# STM32f103.net
KiCad netlist of a schematic drawn in EAGLE
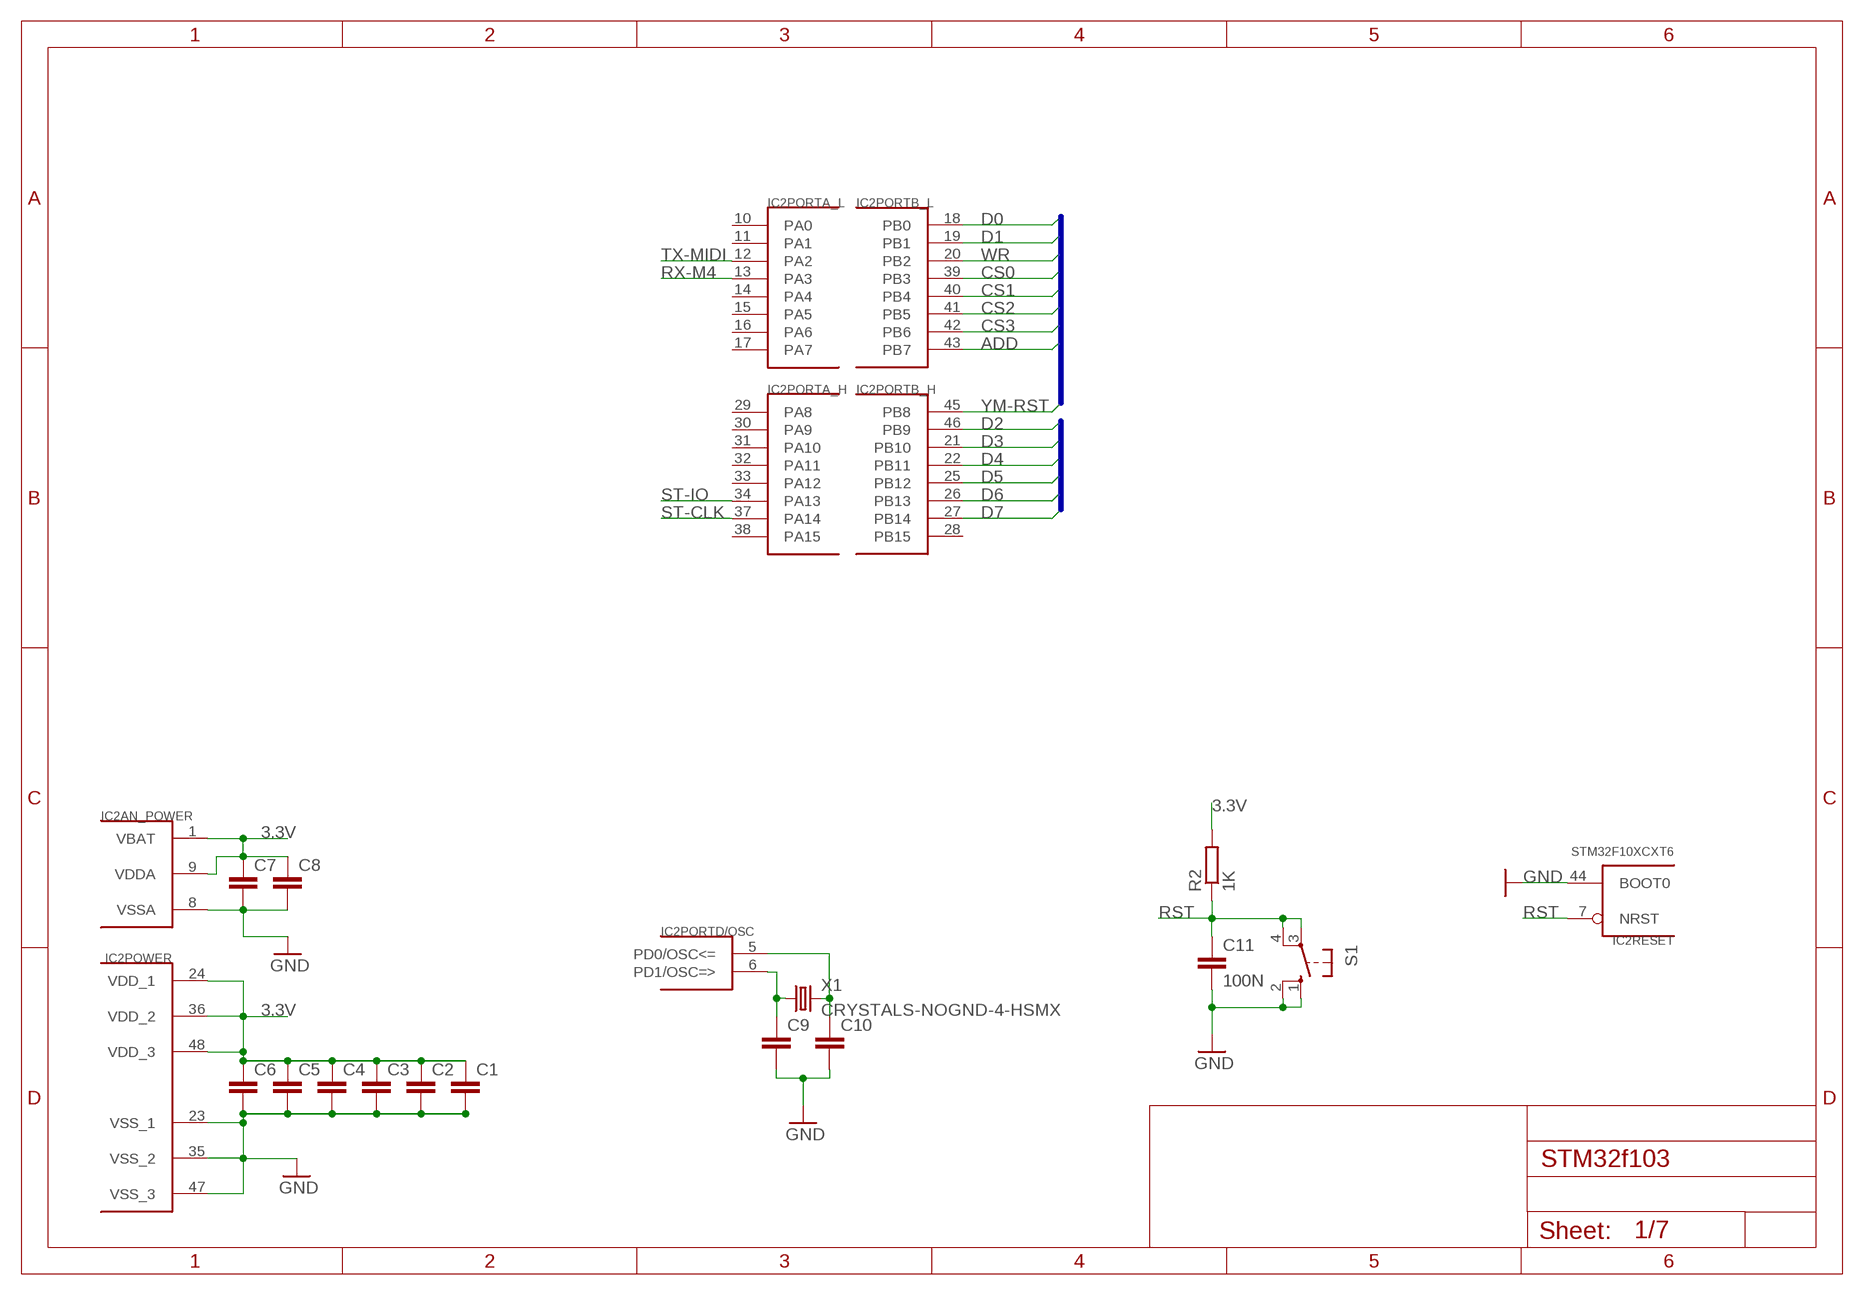
[diagram p0: schematic, sheet 1]
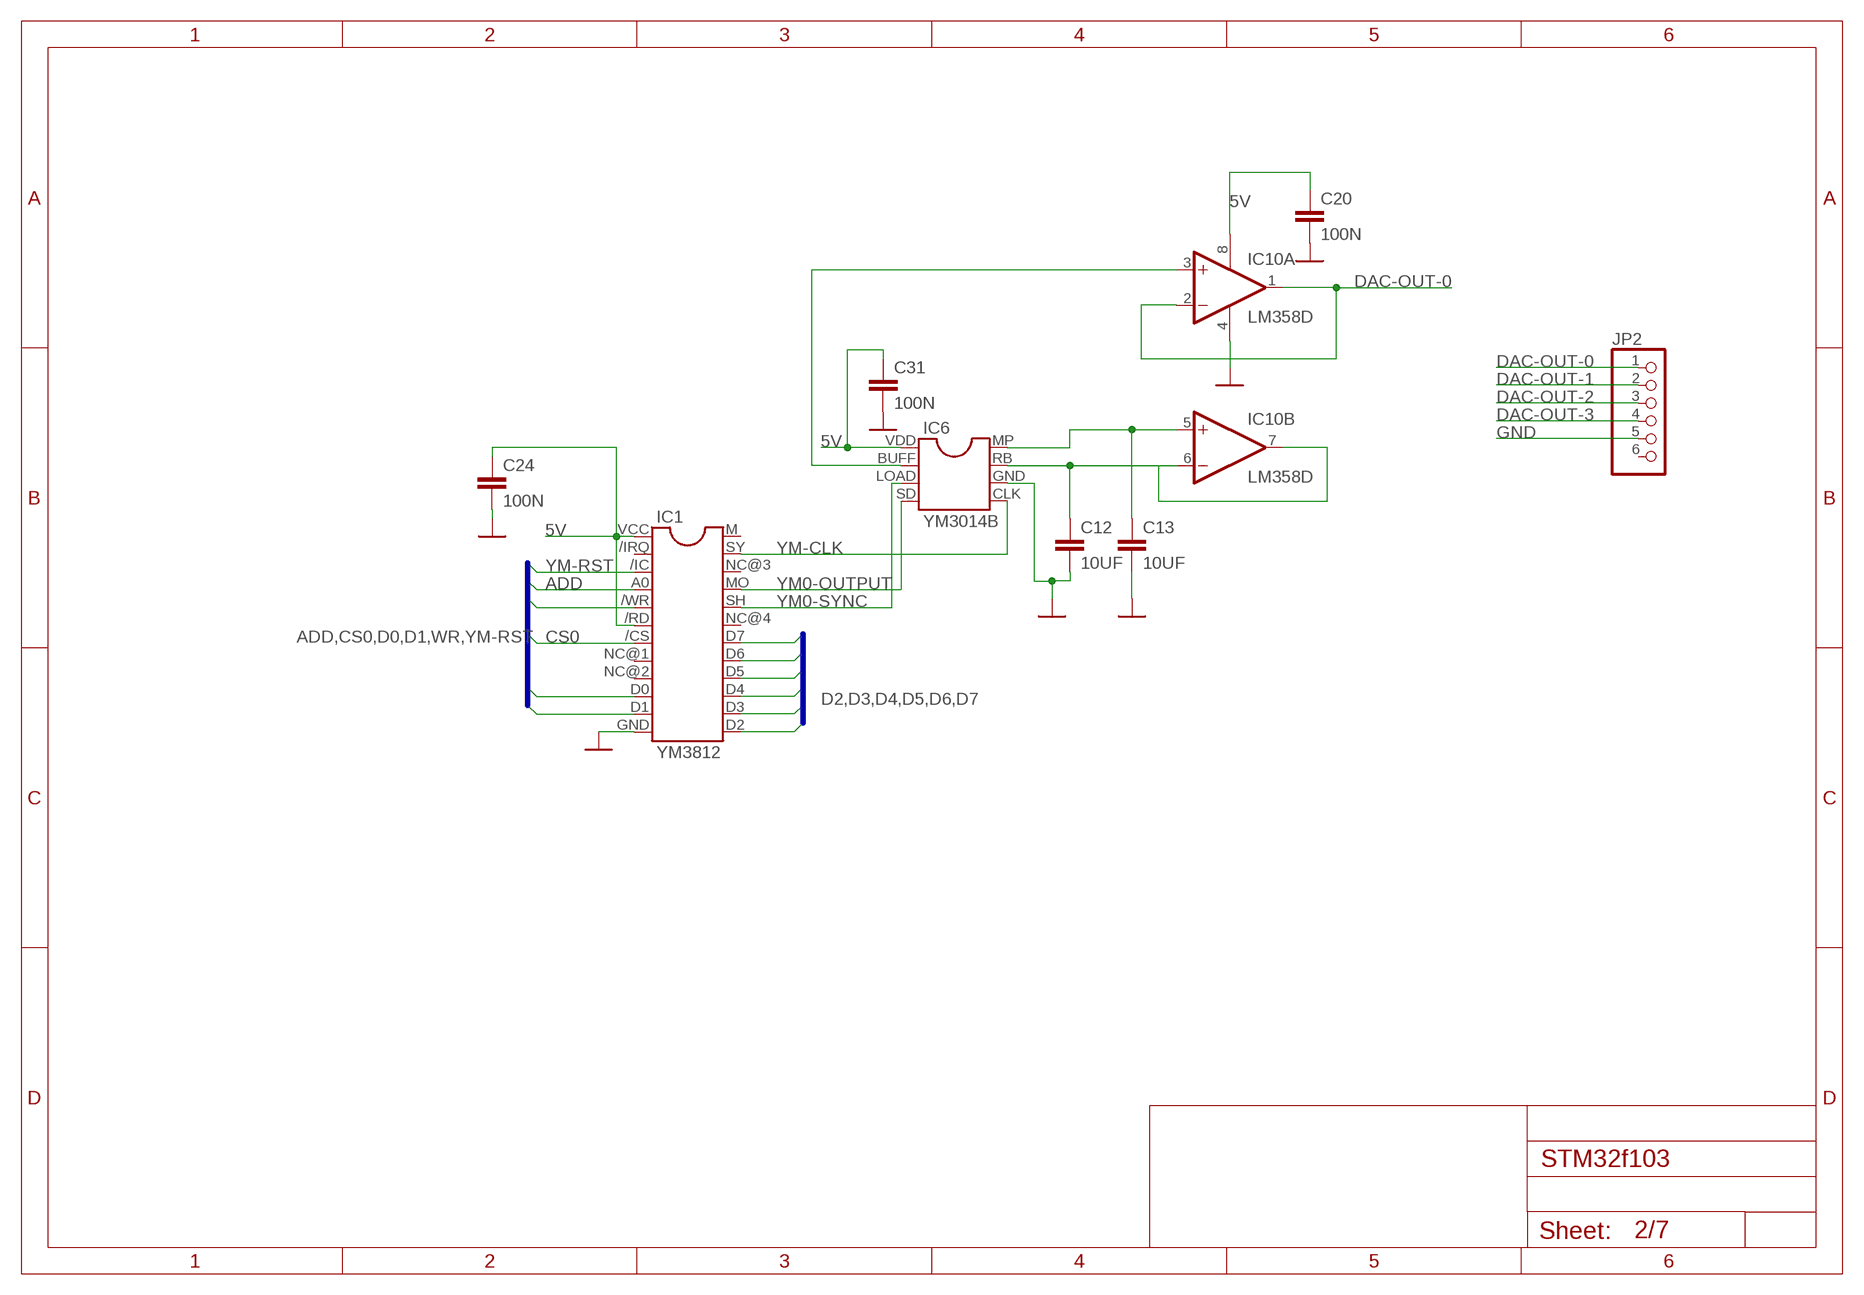
[diagram p1: schematic, sheet 2]
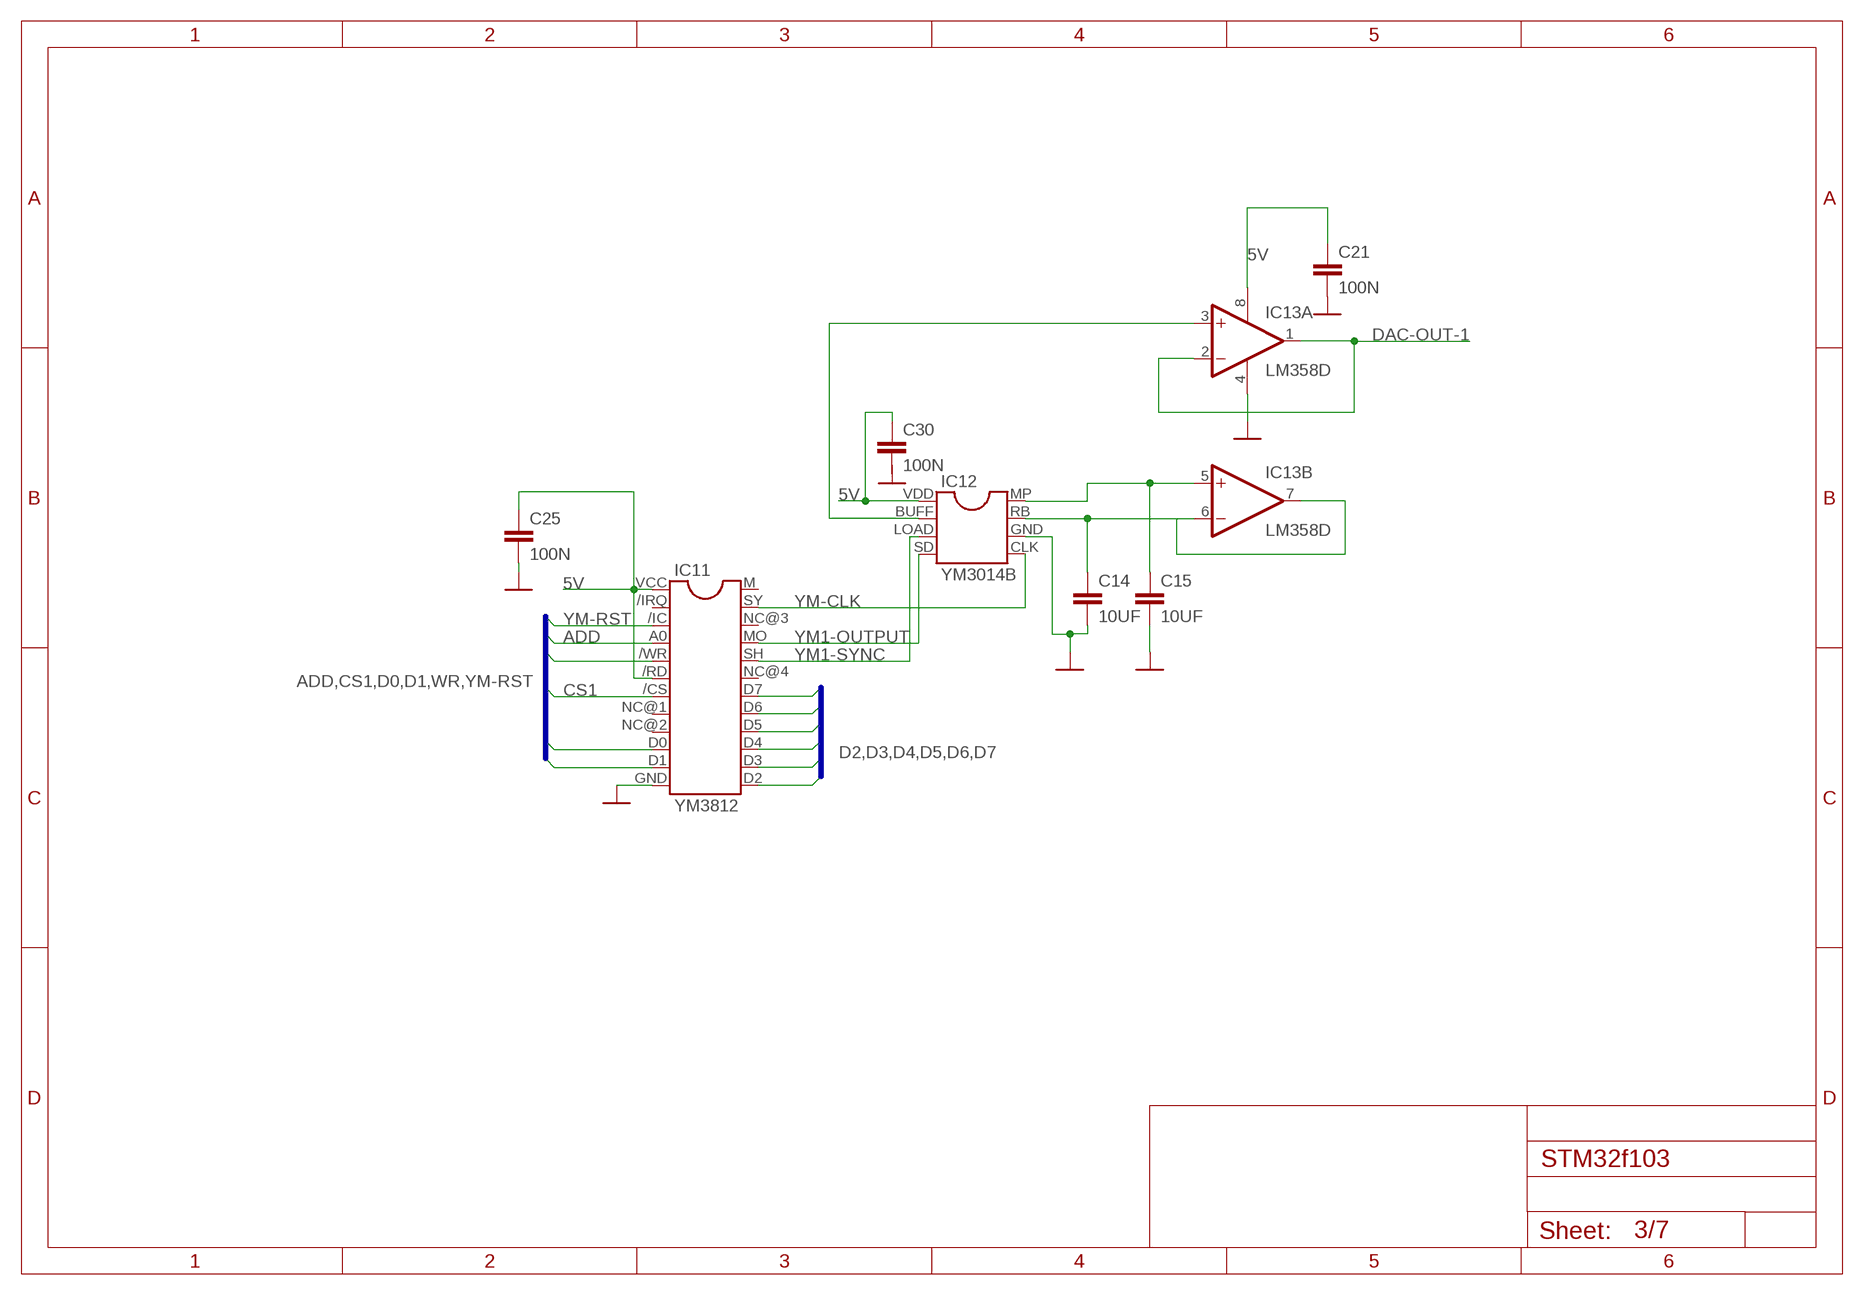
[diagram p2: schematic, sheet 3]
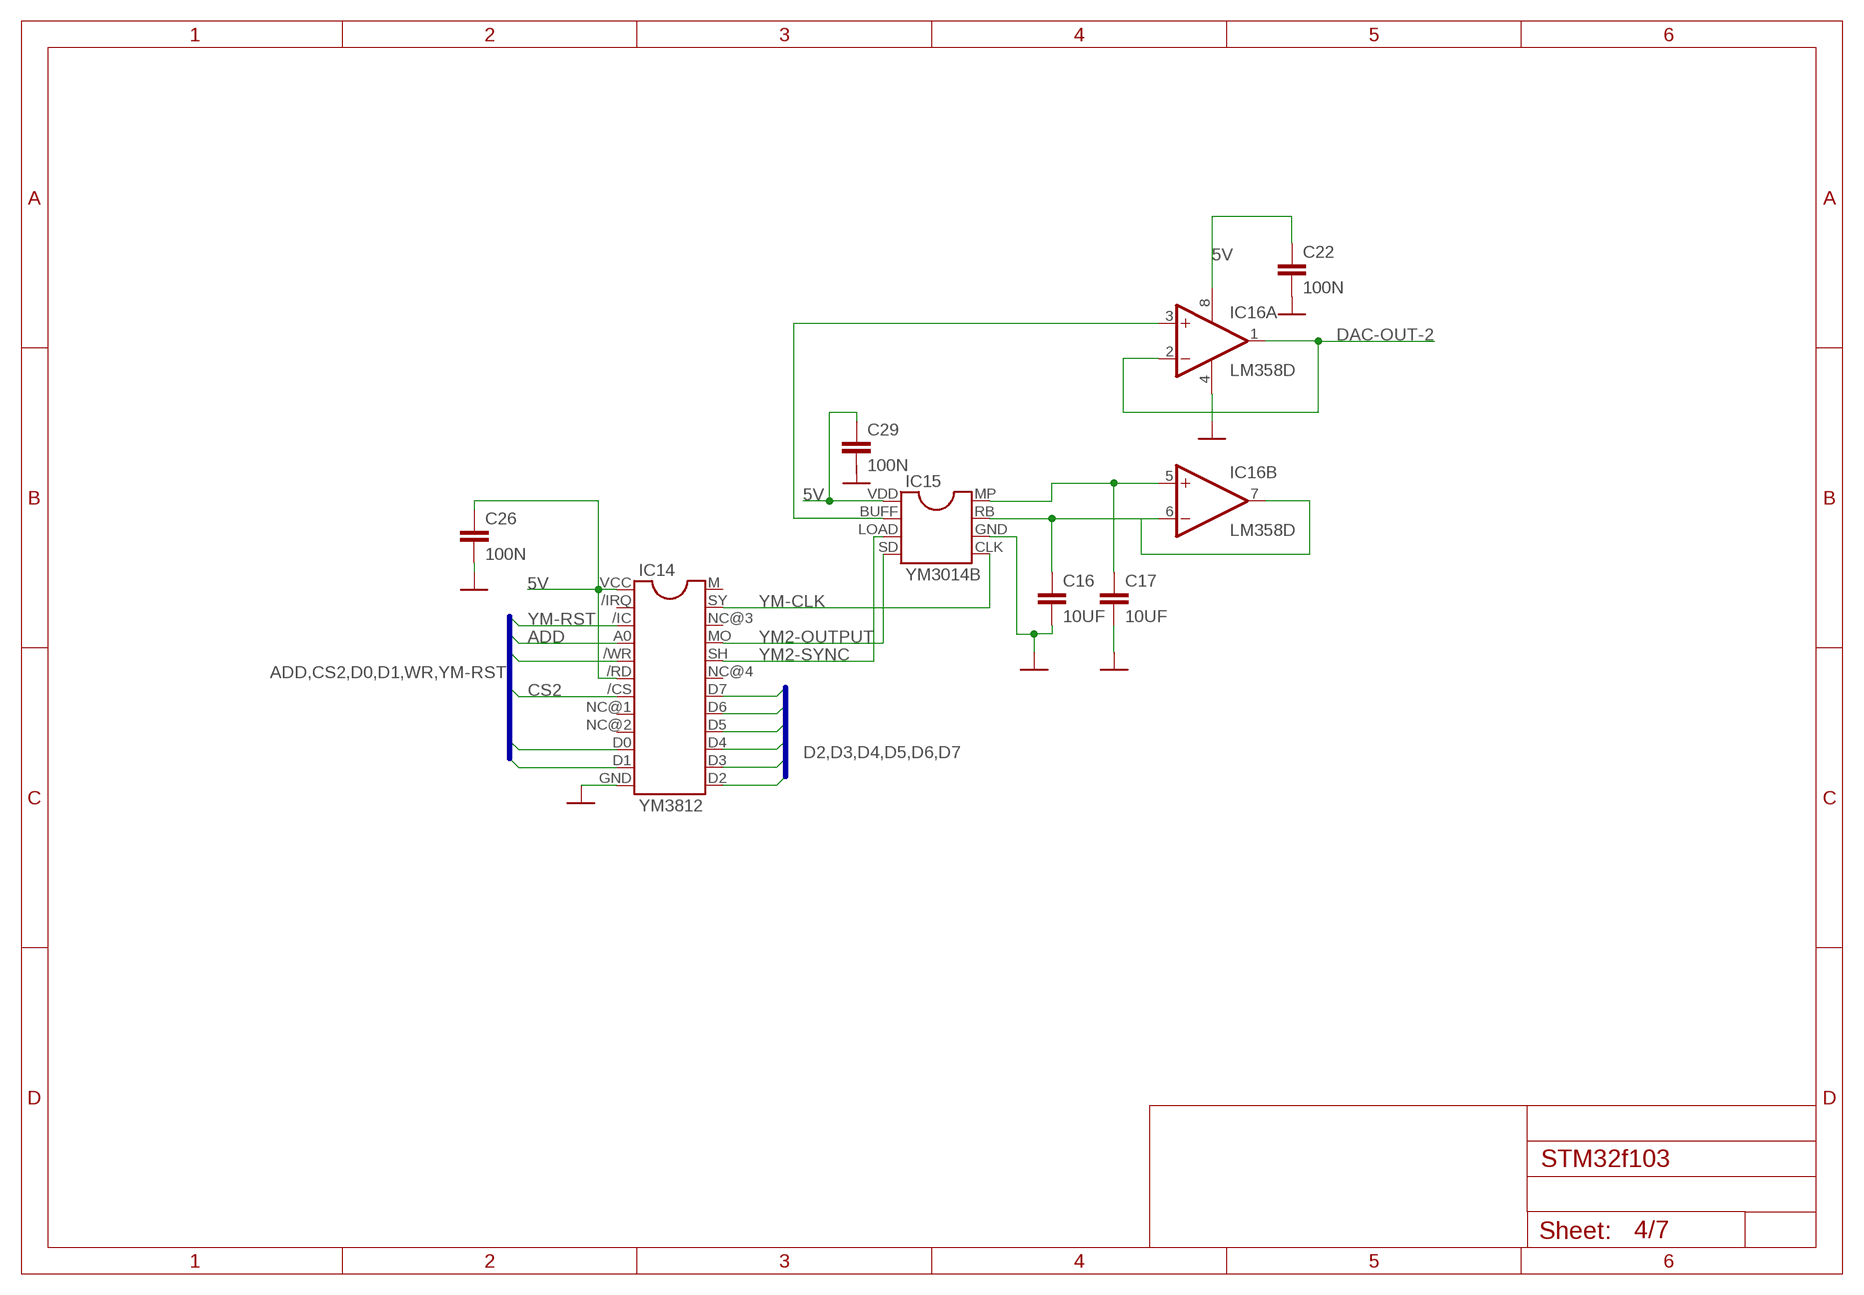
[diagram p3: schematic, sheet 4]
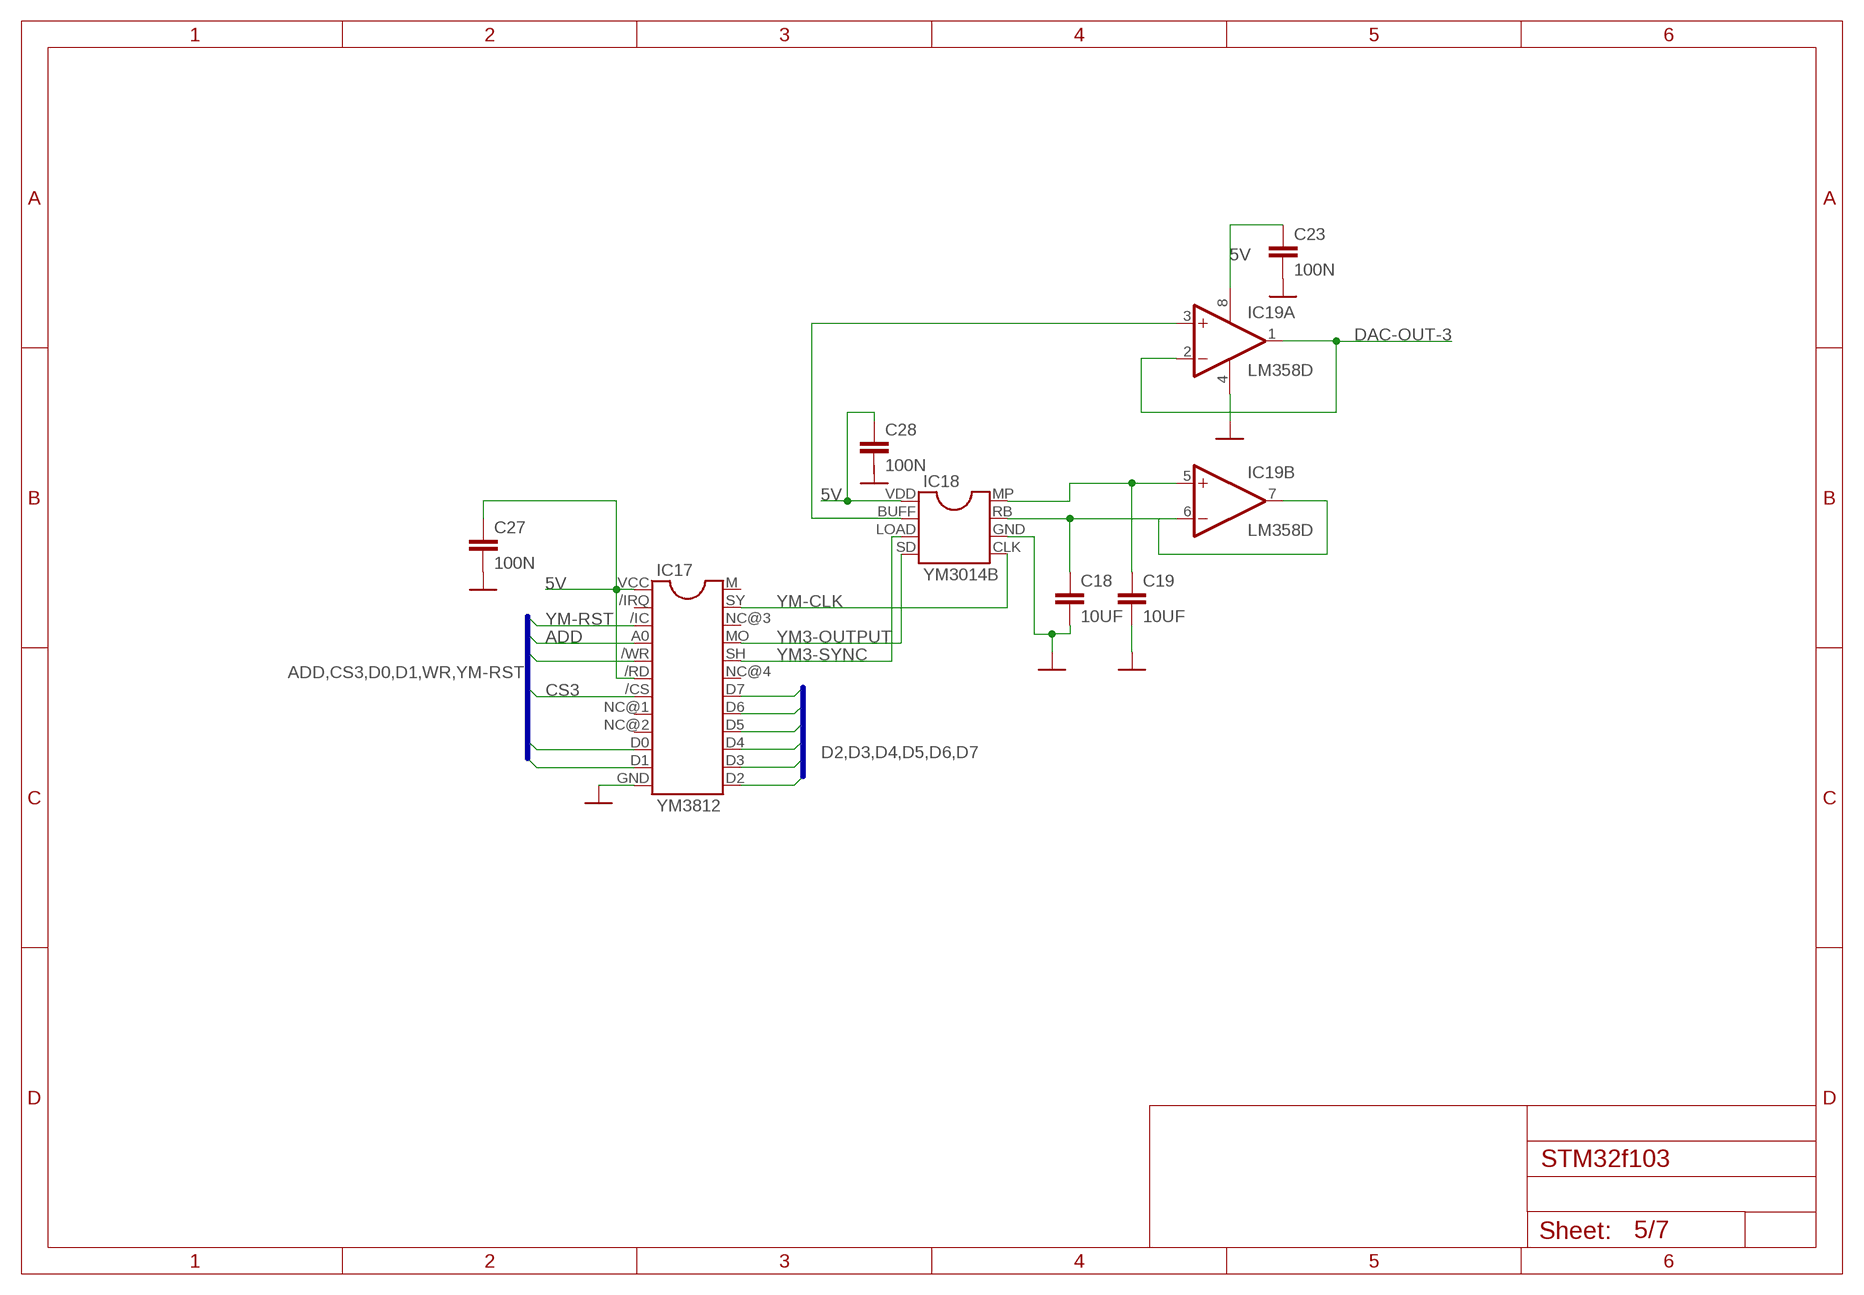
[diagram p4: schematic, sheet 5]
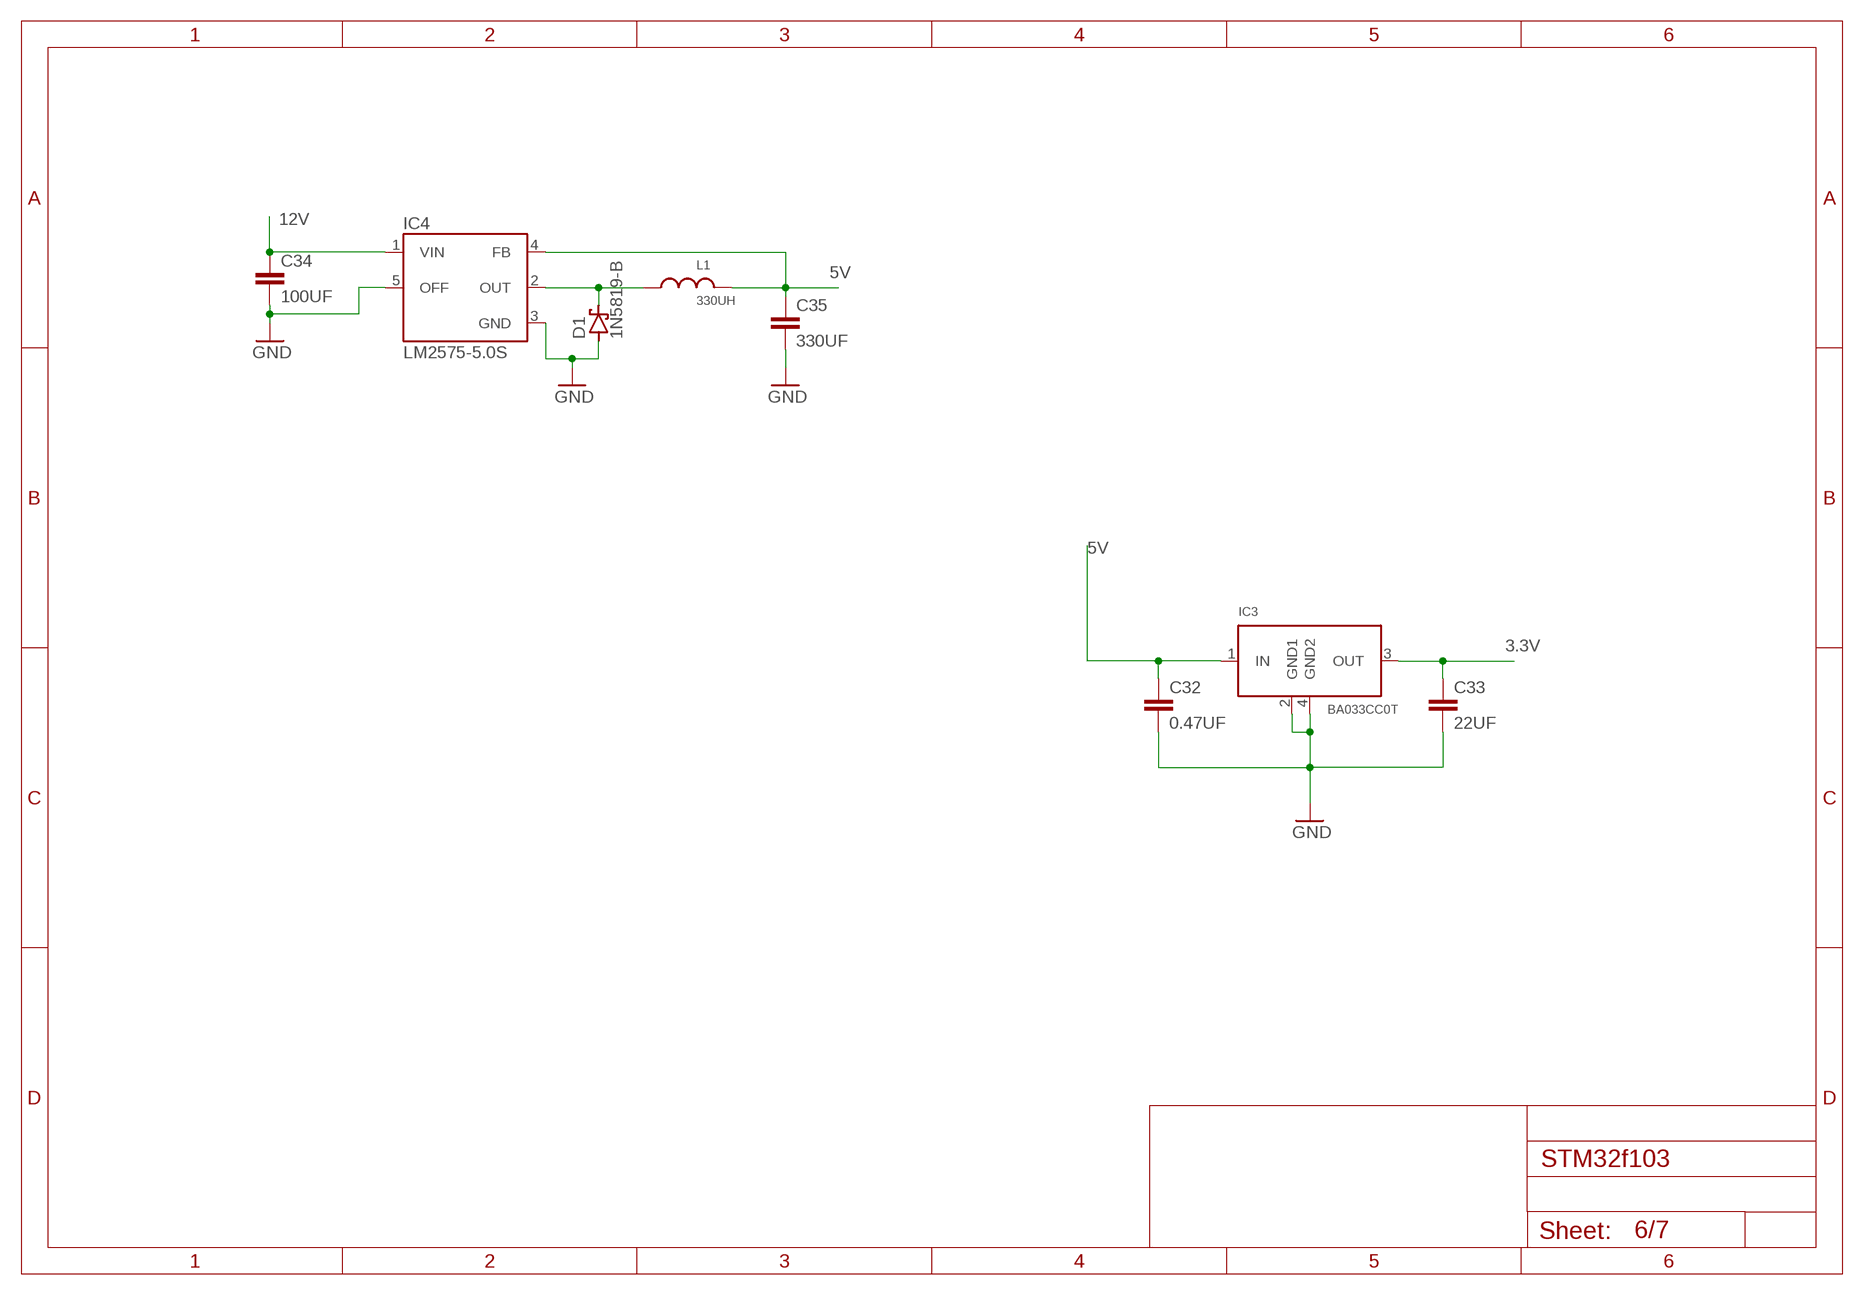
[diagram p5: schematic, sheet 6]
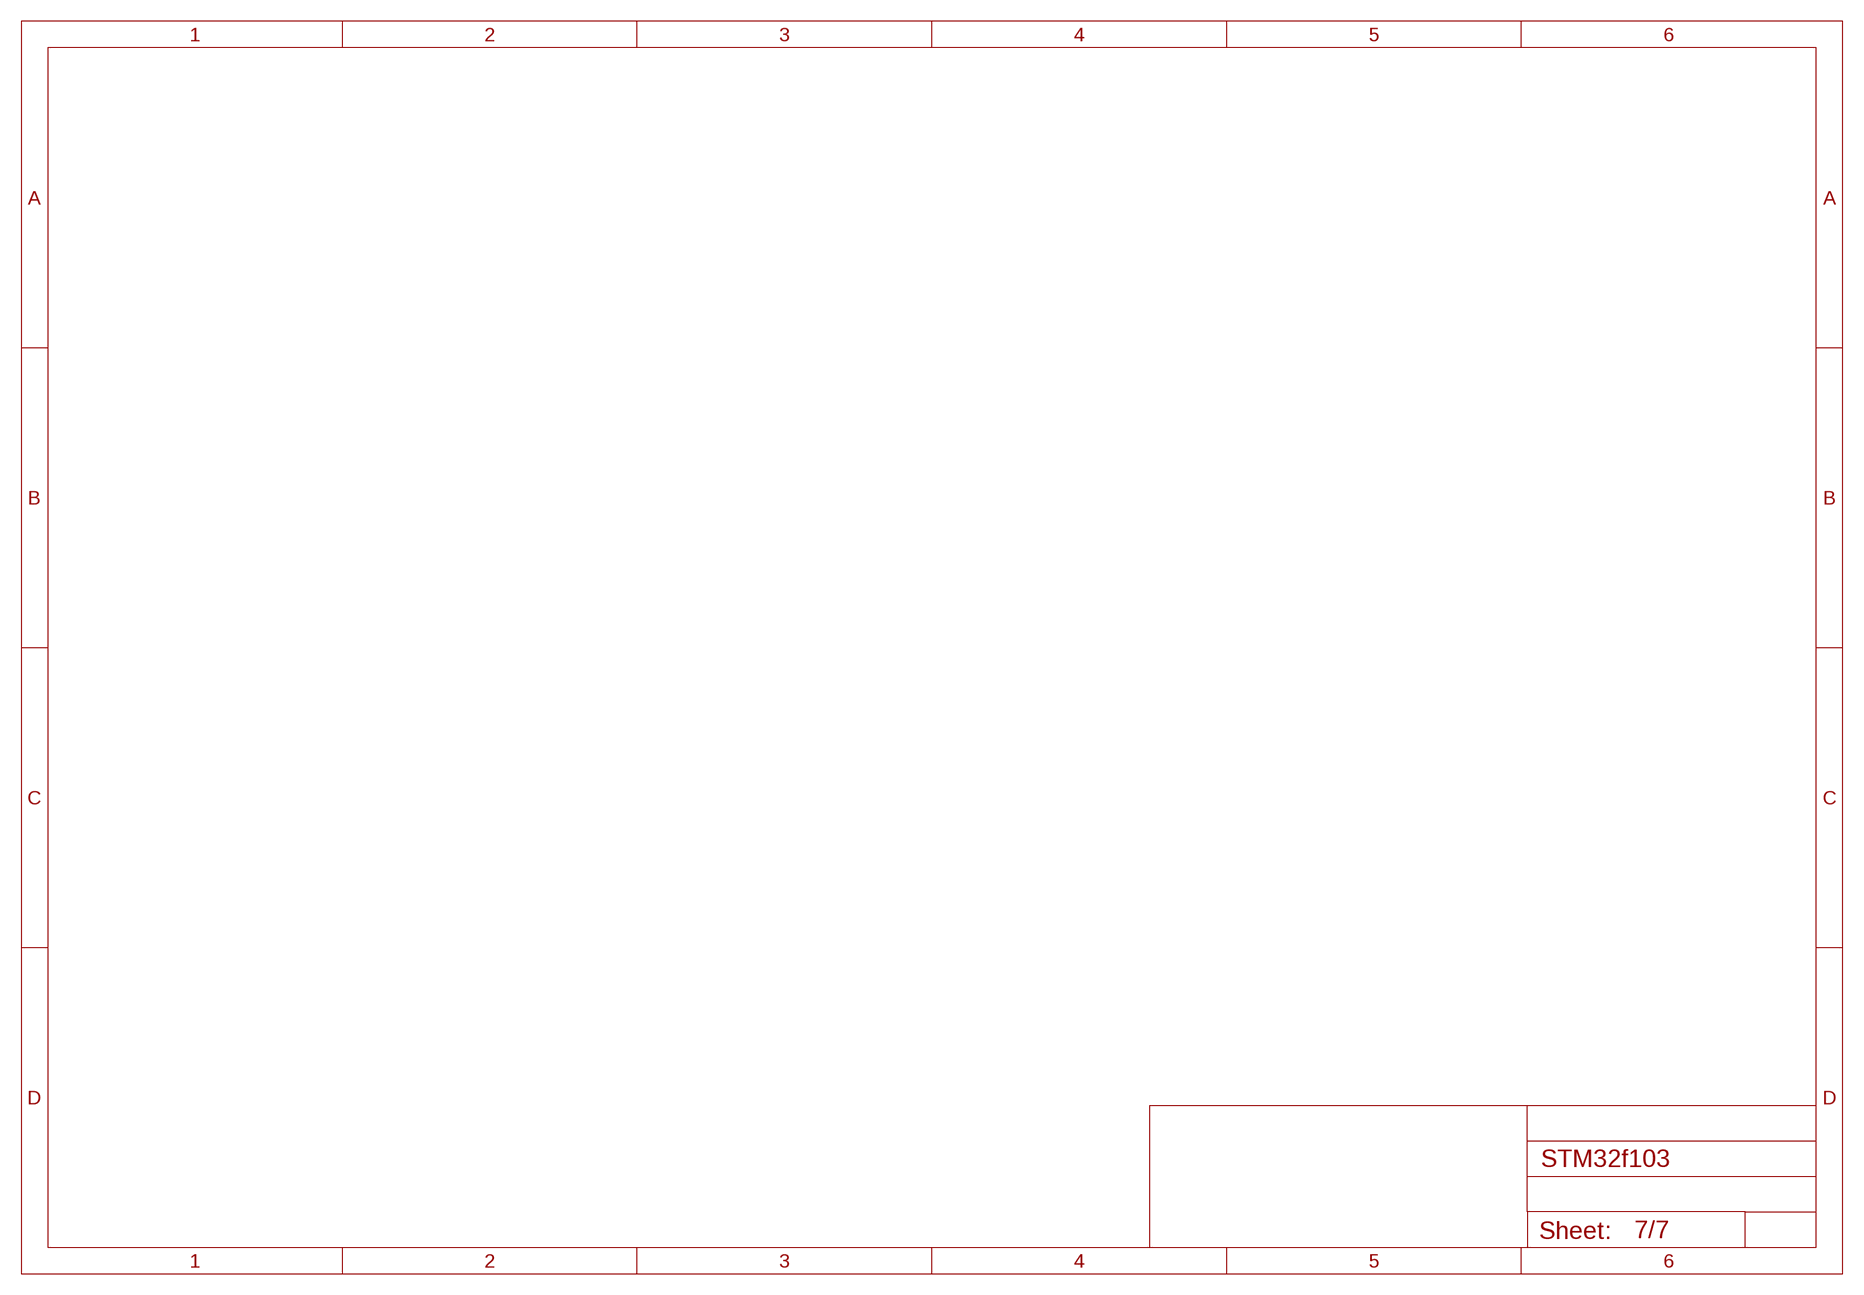
[diagram p6: schematic, sheet 7]

(export (version "E")
  (design (tool "Eeschema 10.0.6"))
  (components
    (comp (ref "C12")
      (value "10UF")
      (footprint "eagle-import:0603-SMD")
      (libsource (lib "eagle-import") (part "10UF"))
    )
    (comp (ref "C13")
      (value "10UF")
      (footprint "eagle-import:0603-SMD")
      (libsource (lib "eagle-import") (part "10UF"))
    )
    (comp (ref "C20")
      (value "100N")
      (footprint "eagle-import:0603-SMD")
      (libsource (lib "eagle-import") (part "100N"))
    )
    (comp (ref "C24")
      (value "100N")
      (footprint "eagle-import:0603-SMD")
      (libsource (lib "eagle-import") (part "100N"))
    )
    (comp (ref "C31")
      (value "100N")
      (footprint "eagle-import:0603-SMD")
      (libsource (lib "eagle-import") (part "100N"))
    )
    (comp (ref "IC1")
      (value "YM3812")
      (footprint "eagle-import:YM3812")
      (libsource (lib "eagle-import") (part "YM3812"))
    )
    (comp (ref "IC6")
      (value "YM3014B")
      (footprint "eagle-import:YM3014B")
      (libsource (lib "eagle-import") (part "YM3014B"))
    )
    (comp (ref "IC10")
      (value "LM358D")
      (footprint "eagle-import:SO08")
      (libsource (lib "eagle-import") (part "LM358D"))
    )
    (comp (ref "JP2")
      (value "PINHD-1X6")
      (footprint "eagle-import:1X06")
      (libsource (lib "eagle-import") (part "PINHD-1X6"))
    )
    (comp (ref "C1")
      (value "C-EUC0603")
      (footprint "eagle-import:C0603")
      (libsource (lib "eagle-import") (part "C-EUC0603"))
    )
    (comp (ref "C2")
      (value "C-EUC0603")
      (footprint "eagle-import:C0603")
      (libsource (lib "eagle-import") (part "C-EUC0603"))
    )
    (comp (ref "C3")
      (value "C-EUC0603")
      (footprint "eagle-import:C0603")
      (libsource (lib "eagle-import") (part "C-EUC0603"))
    )
    (comp (ref "C4")
      (value "C-EUC0603")
      (footprint "eagle-import:C0603")
      (libsource (lib "eagle-import") (part "C-EUC0603"))
    )
    (comp (ref "C5")
      (value "C-EUC0603")
      (footprint "eagle-import:C0603")
      (libsource (lib "eagle-import") (part "C-EUC0603"))
    )
    (comp (ref "C6")
      (value "C-EUC0603")
      (footprint "eagle-import:C0603")
      (libsource (lib "eagle-import") (part "C-EUC0603"))
    )
    (comp (ref "C7")
      (value "C-EUC0603")
      (footprint "eagle-import:C0603")
      (libsource (lib "eagle-import") (part "C-EUC0603"))
    )
    (comp (ref "C8")
      (value "C-EUC0603")
      (footprint "eagle-import:C0603")
      (libsource (lib "eagle-import") (part "C-EUC0603"))
    )
    (comp (ref "C9")
      (value "C-EUC0603")
      (footprint "eagle-import:C0603")
      (libsource (lib "eagle-import") (part "C-EUC0603"))
    )
    (comp (ref "C10")
      (value "C-EUC0603")
      (footprint "eagle-import:C0603")
      (libsource (lib "eagle-import") (part "C-EUC0603"))
    )
    (comp (ref "C11")
      (value "100N")
      (footprint "eagle-import:0603-SMD")
      (libsource (lib "eagle-import") (part "100N"))
    )
    (comp (ref "IC2")
      (value "STM32F10XCXT6")
      (footprint "eagle-import:TQFP48")
      (libsource (lib "eagle-import") (part "STM32F10XCXT6"))
    )
    (comp (ref "R2")
      (value "1K")
      (footprint "eagle-import:0805-SMD")
      (libsource (lib "eagle-import") (part "1K"))
    )
    (comp (ref "S1")
      (value "10-XX")
      (footprint "eagle-import:B3F-10XX")
      (fields (field (name "MPN") "B3F-1000"))
      (libsource (lib "eagle-import") (part "10-XX"))
    )
    (comp (ref "X1")
      (value "CRYSTALS-NOGND-4-HSMX")
      (footprint "eagle-import:HC49-4-HSMX")
      (libsource (lib "eagle-import") (part "CRYSTALS-NOGND-4-HSMX"))
    )
    (comp (ref "C16")
      (value "10UF")
      (footprint "eagle-import:0603-SMD")
      (libsource (lib "eagle-import") (part "10UF"))
    )
    (comp (ref "C17")
      (value "10UF")
      (footprint "eagle-import:0603-SMD")
      (libsource (lib "eagle-import") (part "10UF"))
    )
    (comp (ref "C22")
      (value "100N")
      (footprint "eagle-import:0603-SMD")
      (libsource (lib "eagle-import") (part "100N"))
    )
    (comp (ref "C26")
      (value "100N")
      (footprint "eagle-import:0603-SMD")
      (libsource (lib "eagle-import") (part "100N"))
    )
    (comp (ref "C29")
      (value "100N")
      (footprint "eagle-import:0603-SMD")
      (libsource (lib "eagle-import") (part "100N"))
    )
    (comp (ref "IC14")
      (value "YM3812")
      (footprint "eagle-import:YM3812")
      (libsource (lib "eagle-import") (part "YM3812"))
    )
    (comp (ref "IC15")
      (value "YM3014B")
      (footprint "eagle-import:YM3014B")
      (libsource (lib "eagle-import") (part "YM3014B"))
    )
    (comp (ref "IC16")
      (value "LM358D")
      (footprint "eagle-import:SO08")
      (libsource (lib "eagle-import") (part "LM358D"))
    )
    (comp (ref "C14")
      (value "10UF")
      (footprint "eagle-import:0603-SMD")
      (libsource (lib "eagle-import") (part "10UF"))
    )
    (comp (ref "C15")
      (value "10UF")
      (footprint "eagle-import:0603-SMD")
      (libsource (lib "eagle-import") (part "10UF"))
    )
    (comp (ref "C21")
      (value "100N")
      (footprint "eagle-import:0603-SMD")
      (libsource (lib "eagle-import") (part "100N"))
    )
    (comp (ref "C25")
      (value "100N")
      (footprint "eagle-import:0603-SMD")
      (libsource (lib "eagle-import") (part "100N"))
    )
    (comp (ref "C30")
      (value "100N")
      (footprint "eagle-import:0603-SMD")
      (libsource (lib "eagle-import") (part "100N"))
    )
    (comp (ref "IC11")
      (value "YM3812")
      (footprint "eagle-import:YM3812")
      (libsource (lib "eagle-import") (part "YM3812"))
    )
    (comp (ref "IC12")
      (value "YM3014B")
      (footprint "eagle-import:YM3014B")
      (libsource (lib "eagle-import") (part "YM3014B"))
    )
    (comp (ref "IC13")
      (value "LM358D")
      (footprint "eagle-import:SO08")
      (libsource (lib "eagle-import") (part "LM358D"))
    )
    (comp (ref "C18")
      (value "10UF")
      (footprint "eagle-import:0603-SMD")
      (libsource (lib "eagle-import") (part "10UF"))
    )
    (comp (ref "C19")
      (value "10UF")
      (footprint "eagle-import:0603-SMD")
      (libsource (lib "eagle-import") (part "10UF"))
    )
    (comp (ref "C23")
      (value "100N")
      (footprint "eagle-import:0603-SMD")
      (libsource (lib "eagle-import") (part "100N"))
    )
    (comp (ref "C27")
      (value "100N")
      (footprint "eagle-import:0603-SMD")
      (libsource (lib "eagle-import") (part "100N"))
    )
    (comp (ref "C28")
      (value "100N")
      (footprint "eagle-import:0603-SMD")
      (libsource (lib "eagle-import") (part "100N"))
    )
    (comp (ref "IC17")
      (value "YM3812")
      (footprint "eagle-import:YM3812")
      (libsource (lib "eagle-import") (part "YM3812"))
    )
    (comp (ref "IC18")
      (value "YM3014B")
      (footprint "eagle-import:YM3014B")
      (libsource (lib "eagle-import") (part "YM3014B"))
    )
    (comp (ref "IC19")
      (value "LM358D")
      (footprint "eagle-import:SO08")
      (libsource (lib "eagle-import") (part "LM358D"))
    )
    (comp (ref "C32")
      (value "0.47UF")
      (footprint "eagle-import:0603-SMD")
      (libsource (lib "eagle-import") (part "0.47UF"))
    )
    (comp (ref "C33")
      (value "22UF")
      (footprint "eagle-import:0603-SMD")
      (libsource (lib "eagle-import") (part "22UF"))
    )
    (comp (ref "C34")
      (value "100UF")
      (footprint "eagle-import:0603-SMD")
      (libsource (lib "eagle-import") (part "100UF"))
    )
    (comp (ref "C35")
      (value "330UF")
      (footprint "eagle-import:0603-SMD")
      (libsource (lib "eagle-import") (part "330UF"))
    )
    (comp (ref "D1")
      (value "1N5819-B")
      (footprint "eagle-import:DO41-7.6")
      (libsource (lib "eagle-import") (part "1N5819-B"))
    )
    (comp (ref "IC3")
      (value "BA033CC0T")
      (footprint "eagle-import:SOT223")
      (libsource (lib "eagle-import") (part "VREG_MULTI"))
    )
    (comp (ref "IC4")
      (value "LM2575-5.0S")
      (footprint "eagle-import:TO263-5")
      (libsource (lib "eagle-import") (part "LM2575-5.0S"))
    )
    (comp (ref "L1")
      (value "330UH")
      (footprint "eagle-import:0603-SMD")
      (libsource (lib "eagle-import") (part "330UH"))
    )
  )
  (nets
    (net (code "9") (name "3.3V") (class "Default")
      (node (ref "C1") (pin "1") (pinfunction "1_1") (pintype "passive"))
      (node (ref "C2") (pin "1") (pinfunction "1_1") (pintype "passive"))
      (node (ref "C3") (pin "1") (pinfunction "1_1") (pintype "passive"))
      (node (ref "C33") (pin "1") (pinfunction "1_1") (pintype "passive"))
      (node (ref "C4") (pin "1") (pinfunction "1_1") (pintype "passive"))
      (node (ref "C5") (pin "1") (pinfunction "1_1") (pintype "passive"))
      (node (ref "C6") (pin "1") (pinfunction "1_1") (pintype "passive"))
      (node (ref "C7") (pin "1") (pinfunction "1_1") (pintype "passive"))
      (node (ref "C8") (pin "1") (pinfunction "1_1") (pintype "passive"))
      (node (ref "IC2") (pin "1") (pinfunction "VBAT_1") (pintype "power_in"))
      (node (ref "IC2") (pin "24") (pinfunction "VDD_1_24") (pintype "power_in"))
      (node (ref "IC2") (pin "36") (pinfunction "VDD_2_36") (pintype "power_in"))
      (node (ref "IC2") (pin "48") (pinfunction "VDD_3_48") (pintype "power_in"))
      (node (ref "IC2") (pin "9") (pinfunction "VDDA_9") (pintype "power_in"))
      (node (ref "IC3") (pin "3") (pinfunction "OUT_3") (pintype "power_in"))
      (node (ref "R2") (pin "2") (pinfunction "2_2") (pintype "passive"))
    )
    (net (code "10") (name "5V") (class "Default")
      (node (ref "C20") (pin "1") (pinfunction "1_1") (pintype "passive"))
      (node (ref "C21") (pin "1") (pinfunction "1_1") (pintype "passive"))
      (node (ref "C22") (pin "1") (pinfunction "1_1") (pintype "passive"))
      (node (ref "C23") (pin "1") (pinfunction "1_1") (pintype "passive"))
      (node (ref "C24") (pin "1") (pinfunction "1_1") (pintype "passive"))
      (node (ref "C25") (pin "1") (pinfunction "1_1") (pintype "passive"))
      (node (ref "C26") (pin "1") (pinfunction "1_1") (pintype "passive"))
      (node (ref "C27") (pin "1") (pinfunction "1_1") (pintype "passive"))
      (node (ref "C28") (pin "1") (pinfunction "1_1") (pintype "passive"))
      (node (ref "C29") (pin "1") (pinfunction "1_1") (pintype "passive"))
      (node (ref "C30") (pin "1") (pinfunction "1_1") (pintype "passive"))
      (node (ref "C31") (pin "1") (pinfunction "1_1") (pintype "passive"))
      (node (ref "C32") (pin "1") (pinfunction "1_1") (pintype "passive"))
      (node (ref "C35") (pin "1") (pinfunction "1_1") (pintype "passive"))
      (node (ref "IC1") (pin "/RD") (pinfunction "/RD_/RD") (pintype "passive"))
      (node (ref "IC1") (pin "VCC") (pinfunction "VCC_VCC") (pintype "passive"))
      (node (ref "IC10") (pin "8") (pinfunction "V+_8") (pintype "power_in"))
      (node (ref "IC11") (pin "/RD") (pinfunction "/RD_/RD") (pintype "passive"))
      (node (ref "IC11") (pin "VCC") (pinfunction "VCC_VCC") (pintype "passive"))
      (node (ref "IC12") (pin "VDD") (pinfunction "VDD_VDD") (pintype "passive"))
      (node (ref "IC13") (pin "8") (pinfunction "V+_8") (pintype "power_in"))
      (node (ref "IC14") (pin "/RD") (pinfunction "/RD_/RD") (pintype "passive"))
      (node (ref "IC14") (pin "VCC") (pinfunction "VCC_VCC") (pintype "passive"))
      (node (ref "IC15") (pin "VDD") (pinfunction "VDD_VDD") (pintype "passive"))
      (node (ref "IC16") (pin "8") (pinfunction "V+_8") (pintype "power_in"))
      (node (ref "IC17") (pin "/RD") (pinfunction "/RD_/RD") (pintype "passive"))
      (node (ref "IC17") (pin "VCC") (pinfunction "VCC_VCC") (pintype "passive"))
      (node (ref "IC18") (pin "VDD") (pinfunction "VDD_VDD") (pintype "passive"))
      (node (ref "IC19") (pin "8") (pinfunction "V+_8") (pintype "power_in"))
      (node (ref "IC3") (pin "1") (pinfunction "IN_1") (pintype "power_in"))
      (node (ref "IC4") (pin "4") (pinfunction "FB_4") (pintype "input"))
      (node (ref "IC6") (pin "VDD") (pinfunction "VDD_VDD") (pintype "passive"))
      (node (ref "L1") (pin "1") (pinfunction "P$1_1") (pintype "bidirectional"))
    )
    (net (code "11") (name "12V") (class "Default")
      (node (ref "C34") (pin "1") (pinfunction "1_1") (pintype "passive"))
      (node (ref "IC4") (pin "1") (pinfunction "VIN_1") (pintype "power_in"))
    )
    (net (code "12") (name "ADD") (class "Default")
      (node (ref "IC1") (pin "A0") (pinfunction "A0_A0") (pintype "passive"))
      (node (ref "IC11") (pin "A0") (pinfunction "A0_A0") (pintype "passive"))
      (node (ref "IC14") (pin "A0") (pinfunction "A0_A0") (pintype "passive"))
      (node (ref "IC17") (pin "A0") (pinfunction "A0_A0") (pintype "passive"))
      (node (ref "IC2") (pin "43") (pinfunction "PB7_43") (pintype "bidirectional"))
    )
    (net (code "13") (name "CS0") (class "Default")
      (node (ref "IC1") (pin "/CS") (pinfunction "/CS_/CS") (pintype "passive"))
      (node (ref "IC2") (pin "39") (pinfunction "PB3_39") (pintype "bidirectional"))
    )
    (net (code "14") (name "CS1") (class "Default")
      (node (ref "IC11") (pin "/CS") (pinfunction "/CS_/CS") (pintype "passive"))
      (node (ref "IC2") (pin "40") (pinfunction "PB4_40") (pintype "bidirectional"))
    )
    (net (code "15") (name "CS2") (class "Default")
      (node (ref "IC14") (pin "/CS") (pinfunction "/CS_/CS") (pintype "passive"))
      (node (ref "IC2") (pin "41") (pinfunction "PB5_41") (pintype "bidirectional"))
    )
    (net (code "16") (name "CS3") (class "Default")
      (node (ref "IC17") (pin "/CS") (pinfunction "/CS_/CS") (pintype "passive"))
      (node (ref "IC2") (pin "42") (pinfunction "PB6_42") (pintype "bidirectional"))
    )
    (net (code "17") (name "D0") (class "Default")
      (node (ref "IC1") (pin "D0") (pinfunction "D0_D0") (pintype "passive"))
      (node (ref "IC11") (pin "D0") (pinfunction "D0_D0") (pintype "passive"))
      (node (ref "IC14") (pin "D0") (pinfunction "D0_D0") (pintype "passive"))
      (node (ref "IC17") (pin "D0") (pinfunction "D0_D0") (pintype "passive"))
      (node (ref "IC2") (pin "18") (pinfunction "PB0_18") (pintype "bidirectional"))
    )
    (net (code "18") (name "D1") (class "Default")
      (node (ref "IC1") (pin "D1") (pinfunction "D1_D1") (pintype "passive"))
      (node (ref "IC11") (pin "D1") (pinfunction "D1_D1") (pintype "passive"))
      (node (ref "IC14") (pin "D1") (pinfunction "D1_D1") (pintype "passive"))
      (node (ref "IC17") (pin "D1") (pinfunction "D1_D1") (pintype "passive"))
      (node (ref "IC2") (pin "19") (pinfunction "PB1_19") (pintype "bidirectional"))
    )
    (net (code "19") (name "D2") (class "Default")
      (node (ref "IC1") (pin "D2") (pinfunction "D2_D2") (pintype "passive"))
      (node (ref "IC11") (pin "D2") (pinfunction "D2_D2") (pintype "passive"))
      (node (ref "IC14") (pin "D2") (pinfunction "D2_D2") (pintype "passive"))
      (node (ref "IC17") (pin "D2") (pinfunction "D2_D2") (pintype "passive"))
      (node (ref "IC2") (pin "46") (pinfunction "PB9_46") (pintype "bidirectional"))
    )
    (net (code "20") (name "D3") (class "Default")
      (node (ref "IC1") (pin "D3") (pinfunction "D3_D3") (pintype "passive"))
      (node (ref "IC11") (pin "D3") (pinfunction "D3_D3") (pintype "passive"))
      (node (ref "IC14") (pin "D3") (pinfunction "D3_D3") (pintype "passive"))
      (node (ref "IC17") (pin "D3") (pinfunction "D3_D3") (pintype "passive"))
      (node (ref "IC2") (pin "21") (pinfunction "PB10_21") (pintype "bidirectional"))
    )
    (net (code "21") (name "D4") (class "Default")
      (node (ref "IC1") (pin "D4") (pinfunction "D4_D4") (pintype "passive"))
      (node (ref "IC11") (pin "D4") (pinfunction "D4_D4") (pintype "passive"))
      (node (ref "IC14") (pin "D4") (pinfunction "D4_D4") (pintype "passive"))
      (node (ref "IC17") (pin "D4") (pinfunction "D4_D4") (pintype "passive"))
      (node (ref "IC2") (pin "22") (pinfunction "PB11_22") (pintype "bidirectional"))
    )
    (net (code "22") (name "D5") (class "Default")
      (node (ref "IC1") (pin "D5") (pinfunction "D5_D5") (pintype "passive"))
      (node (ref "IC11") (pin "D5") (pinfunction "D5_D5") (pintype "passive"))
      (node (ref "IC14") (pin "D5") (pinfunction "D5_D5") (pintype "passive"))
      (node (ref "IC17") (pin "D5") (pinfunction "D5_D5") (pintype "passive"))
      (node (ref "IC2") (pin "25") (pinfunction "PB12_25") (pintype "bidirectional"))
    )
    (net (code "23") (name "D6") (class "Default")
      (node (ref "IC1") (pin "D6") (pinfunction "D6_D6") (pintype "passive"))
      (node (ref "IC11") (pin "D6") (pinfunction "D6_D6") (pintype "passive"))
      (node (ref "IC14") (pin "D6") (pinfunction "D6_D6") (pintype "passive"))
      (node (ref "IC17") (pin "D6") (pinfunction "D6_D6") (pintype "passive"))
      (node (ref "IC2") (pin "26") (pinfunction "PB13_26") (pintype "bidirectional"))
    )
    (net (code "24") (name "D7") (class "Default")
      (node (ref "IC1") (pin "D7") (pinfunction "D7_D7") (pintype "passive"))
      (node (ref "IC11") (pin "D7") (pinfunction "D7_D7") (pintype "passive"))
      (node (ref "IC14") (pin "D7") (pinfunction "D7_D7") (pintype "passive"))
      (node (ref "IC17") (pin "D7") (pinfunction "D7_D7") (pintype "passive"))
      (node (ref "IC2") (pin "27") (pinfunction "PB14_27") (pintype "bidirectional"))
    )
    (net (code "25") (name "DAC-OUT-0") (class "Default")
      (node (ref "IC10") (pin "1") (pinfunction "OUT_1") (pintype "output"))
      (node (ref "IC10") (pin "2") (pinfunction "-IN_2") (pintype "input"))
      (node (ref "JP2") (pin "1") (pinfunction "1_1") (pintype "passive"))
    )
    (net (code "26") (name "DAC-OUT-1") (class "Default")
      (node (ref "IC13") (pin "1") (pinfunction "OUT_1") (pintype "output"))
      (node (ref "IC13") (pin "2") (pinfunction "-IN_2") (pintype "input"))
      (node (ref "JP2") (pin "2") (pinfunction "2_2") (pintype "passive"))
    )
    (net (code "27") (name "DAC-OUT-2") (class "Default")
      (node (ref "IC16") (pin "1") (pinfunction "OUT_1") (pintype "output"))
      (node (ref "IC16") (pin "2") (pinfunction "-IN_2") (pintype "input"))
      (node (ref "JP2") (pin "3") (pinfunction "3_3") (pintype "passive"))
    )
    (net (code "28") (name "DAC-OUT-3") (class "Default")
      (node (ref "IC19") (pin "1") (pinfunction "OUT_1") (pintype "output"))
      (node (ref "IC19") (pin "2") (pinfunction "-IN_2") (pintype "input"))
      (node (ref "JP2") (pin "4") (pinfunction "4_4") (pintype "passive"))
    )
    (net (code "29") (name "GND") (class "Default")
      (node (ref "C1") (pin "2") (pinfunction "2_2") (pintype "passive"))
      (node (ref "C10") (pin "2") (pinfunction "2_2") (pintype "passive"))
      (node (ref "C11") (pin "2") (pinfunction "2_2") (pintype "passive"))
      (node (ref "C12") (pin "2") (pinfunction "2_2") (pintype "passive"))
      (node (ref "C13") (pin "2") (pinfunction "2_2") (pintype "passive"))
      (node (ref "C14") (pin "2") (pinfunction "2_2") (pintype "passive"))
      (node (ref "C15") (pin "2") (pinfunction "2_2") (pintype "passive"))
      (node (ref "C16") (pin "2") (pinfunction "2_2") (pintype "passive"))
      (node (ref "C17") (pin "2") (pinfunction "2_2") (pintype "passive"))
      (node (ref "C18") (pin "2") (pinfunction "2_2") (pintype "passive"))
      (node (ref "C19") (pin "2") (pinfunction "2_2") (pintype "passive"))
      (node (ref "C2") (pin "2") (pinfunction "2_2") (pintype "passive"))
      (node (ref "C20") (pin "2") (pinfunction "2_2") (pintype "passive"))
      (node (ref "C21") (pin "2") (pinfunction "2_2") (pintype "passive"))
      (node (ref "C22") (pin "2") (pinfunction "2_2") (pintype "passive"))
      (node (ref "C23") (pin "2") (pinfunction "2_2") (pintype "passive"))
      (node (ref "C24") (pin "2") (pinfunction "2_2") (pintype "passive"))
      (node (ref "C25") (pin "2") (pinfunction "2_2") (pintype "passive"))
      (node (ref "C26") (pin "2") (pinfunction "2_2") (pintype "passive"))
      (node (ref "C27") (pin "2") (pinfunction "2_2") (pintype "passive"))
      (node (ref "C3") (pin "2") (pinfunction "2_2") (pintype "passive"))
      (node (ref "C31") (pin "2") (pinfunction "2_2") (pintype "passive"))
      (node (ref "C32") (pin "2") (pinfunction "2_2") (pintype "passive"))
      (node (ref "C33") (pin "2") (pinfunction "2_2") (pintype "passive"))
      (node (ref "C34") (pin "2") (pinfunction "2_2") (pintype "passive"))
      (node (ref "C35") (pin "2") (pinfunction "2_2") (pintype "passive"))
      (node (ref "C4") (pin "2") (pinfunction "2_2") (pintype "passive"))
      (node (ref "C5") (pin "2") (pinfunction "2_2") (pintype "passive"))
      (node (ref "C6") (pin "2") (pinfunction "2_2") (pintype "passive"))
      (node (ref "C7") (pin "2") (pinfunction "2_2") (pintype "passive"))
      (node (ref "C8") (pin "2") (pinfunction "2_2") (pintype "passive"))
      (node (ref "C9") (pin "2") (pinfunction "2_2") (pintype "passive"))
      (node (ref "D1") (pin "A") (pinfunction "A_A") (pintype "passive"))
      (node (ref "IC1") (pin "GND") (pinfunction "GND_GND") (pintype "passive"))
      (node (ref "IC10") (pin "4") (pinfunction "V-_4") (pintype "power_in"))
      (node (ref "IC11") (pin "GND") (pinfunction "GND_GND") (pintype "passive"))
      (node (ref "IC12") (pin "GND") (pinfunction "GND_GND") (pintype "passive"))
      (node (ref "IC13") (pin "4") (pinfunction "V-_4") (pintype "power_in"))
      (node (ref "IC14") (pin "GND") (pinfunction "GND_GND") (pintype "passive"))
      (node (ref "IC15") (pin "GND") (pinfunction "GND_GND") (pintype "passive"))
      (node (ref "IC16") (pin "4") (pinfunction "V-_4") (pintype "power_in"))
      (node (ref "IC17") (pin "GND") (pinfunction "GND_GND") (pintype "passive"))
      (node (ref "IC18") (pin "GND") (pinfunction "GND_GND") (pintype "passive"))
      (node (ref "IC19") (pin "4") (pinfunction "V-_4") (pintype "power_in"))
      (node (ref "IC2") (pin "23") (pinfunction "VSS_1_23") (pintype "power_in"))
      (node (ref "IC2") (pin "35") (pinfunction "VSS_2_35") (pintype "power_in"))
      (node (ref "IC2") (pin "44") (pinfunction "BOOT0_44") (pintype "input"))
      (node (ref "IC2") (pin "47") (pinfunction "VSS_3_47") (pintype "power_in"))
      (node (ref "IC2") (pin "8") (pinfunction "VSSA_8") (pintype "power_in"))
      (node (ref "IC3") (pin "2") (pinfunction "GND1_2") (pintype "power_in"))
      (node (ref "IC3") (pin "4") (pinfunction "GND2_4") (pintype "power_in"))
      (node (ref "IC4") (pin "3") (pinfunction "GND_3") (pintype "power_in"))
      (node (ref "IC4") (pin "5") (pinfunction "OFF_5") (pintype "input"))
      (node (ref "IC6") (pin "GND") (pinfunction "GND_GND") (pintype "passive"))
      (node (ref "JP2") (pin "5") (pinfunction "5_5") (pintype "passive"))
      (node (ref "S1") (pin "1") (pinfunction "S_1") (pintype "passive"))
      (node (ref "S1") (pin "2") (pinfunction "S1_2") (pintype "passive"))
    )
    (net (code "30") (name "Net-(IC2G-PD0{slash}OSC<=)") (class "Default")
      (node (ref "C10") (pin "1") (pinfunction "1_1") (pintype "passive"))
      (node (ref "IC2") (pin "5") (pinfunction "PD0/OSC<=_5") (pintype "bidirectional"))
      (node (ref "X1") (pin "2") (pinfunction "2_2") (pintype "passive"))
    )
    (net (code "31") (name "Net-(IC2G-PD1{slash}OSC=>)") (class "Default")
      (node (ref "C9") (pin "1") (pinfunction "1_1") (pintype "passive"))
      (node (ref "IC2") (pin "6") (pinfunction "PD1/OSC=>_6") (pintype "bidirectional"))
      (node (ref "X1") (pin "1") (pinfunction "1_1") (pintype "passive"))
    )
    (net (code "32") (name "Net-(IC4-OUT)") (class "Default")
      (node (ref "D1") (pin "C") (pinfunction "C_C") (pintype "passive"))
      (node (ref "IC4") (pin "2") (pinfunction "OUT_2") (pintype "output"))
      (node (ref "L1") (pin "2") (pinfunction "P$2_2") (pintype "bidirectional"))
    )
    (net (code "33") (name "Net-(IC10A-+IN)") (class "Default")
      (node (ref "IC10") (pin "3") (pinfunction "+IN_3") (pintype "input"))
      (node (ref "IC6") (pin "BUFF") (pinfunction "BUFF_BUFF") (pintype "passive"))
    )
    (net (code "34") (name "Net-(IC10B-+IN)") (class "Default")
      (node (ref "C13") (pin "1") (pinfunction "1_1") (pintype "passive"))
      (node (ref "IC10") (pin "5") (pinfunction "+IN_5") (pintype "input"))
      (node (ref "IC6") (pin "MP") (pinfunction "MP_MP") (pintype "passive"))
    )
    (net (code "35") (name "Net-(IC10B--IN)") (class "Default")
      (node (ref "C12") (pin "1") (pinfunction "1_1") (pintype "passive"))
      (node (ref "IC10") (pin "6") (pinfunction "-IN_6") (pintype "input"))
      (node (ref "IC10") (pin "7") (pinfunction "OUT_7") (pintype "output"))
      (node (ref "IC6") (pin "RB") (pinfunction "RB_RB") (pintype "passive"))
    )
    (net (code "36") (name "Net-(IC13A-+IN)") (class "Default")
      (node (ref "IC12") (pin "BUFF") (pinfunction "BUFF_BUFF") (pintype "passive"))
      (node (ref "IC13") (pin "3") (pinfunction "+IN_3") (pintype "input"))
    )
    (net (code "37") (name "Net-(IC13B-+IN)") (class "Default")
      (node (ref "C15") (pin "1") (pinfunction "1_1") (pintype "passive"))
      (node (ref "IC12") (pin "MP") (pinfunction "MP_MP") (pintype "passive"))
      (node (ref "IC13") (pin "5") (pinfunction "+IN_5") (pintype "input"))
    )
    (net (code "38") (name "Net-(IC13B--IN)") (class "Default")
      (node (ref "C14") (pin "1") (pinfunction "1_1") (pintype "passive"))
      (node (ref "IC12") (pin "RB") (pinfunction "RB_RB") (pintype "passive"))
      (node (ref "IC13") (pin "6") (pinfunction "-IN_6") (pintype "input"))
      (node (ref "IC13") (pin "7") (pinfunction "OUT_7") (pintype "output"))
    )
    (net (code "39") (name "Net-(IC16A-+IN)") (class "Default")
      (node (ref "IC15") (pin "BUFF") (pinfunction "BUFF_BUFF") (pintype "passive"))
      (node (ref "IC16") (pin "3") (pinfunction "+IN_3") (pintype "input"))
    )
    (net (code "40") (name "Net-(IC16B-+IN)") (class "Default")
      (node (ref "C17") (pin "1") (pinfunction "1_1") (pintype "passive"))
      (node (ref "IC15") (pin "MP") (pinfunction "MP_MP") (pintype "passive"))
      (node (ref "IC16") (pin "5") (pinfunction "+IN_5") (pintype "input"))
    )
    (net (code "41") (name "Net-(IC16B--IN)") (class "Default")
      (node (ref "C16") (pin "1") (pinfunction "1_1") (pintype "passive"))
      (node (ref "IC15") (pin "RB") (pinfunction "RB_RB") (pintype "passive"))
      (node (ref "IC16") (pin "6") (pinfunction "-IN_6") (pintype "input"))
      (node (ref "IC16") (pin "7") (pinfunction "OUT_7") (pintype "output"))
    )
    (net (code "42") (name "Net-(IC19A-+IN)") (class "Default")
      (node (ref "IC18") (pin "BUFF") (pinfunction "BUFF_BUFF") (pintype "passive"))
      (node (ref "IC19") (pin "3") (pinfunction "+IN_3") (pintype "input"))
    )
    (net (code "43") (name "Net-(IC19B-+IN)") (class "Default")
      (node (ref "C19") (pin "1") (pinfunction "1_1") (pintype "passive"))
      (node (ref "IC18") (pin "MP") (pinfunction "MP_MP") (pintype "passive"))
      (node (ref "IC19") (pin "5") (pinfunction "+IN_5") (pintype "input"))
    )
    (net (code "44") (name "Net-(IC19B--IN)") (class "Default")
      (node (ref "C18") (pin "1") (pinfunction "1_1") (pintype "passive"))
      (node (ref "IC18") (pin "RB") (pinfunction "RB_RB") (pintype "passive"))
      (node (ref "IC19") (pin "6") (pinfunction "-IN_6") (pintype "input"))
      (node (ref "IC19") (pin "7") (pinfunction "OUT_7") (pintype "output"))
    )
    (net (code "45") (name "RST") (class "Default")
      (node (ref "C11") (pin "1") (pinfunction "1_1") (pintype "passive"))
      (node (ref "IC2") (pin "7") (pinfunction "NRST_7") (pintype "input"))
      (node (ref "R2") (pin "1") (pinfunction "1_1") (pintype "passive"))
      (node (ref "S1") (pin "3") (pinfunction "P_3") (pintype "passive"))
      (node (ref "S1") (pin "4") (pinfunction "P1_4") (pintype "passive"))
    )
    (net (code "46") (name "RX-M4") (class "Default")
      (node (ref "IC2") (pin "13") (pinfunction "PA3_13") (pintype "bidirectional"))
    )
    (net (code "47") (name "ST-CLK") (class "Default")
      (node (ref "IC2") (pin "37") (pinfunction "PA14_37") (pintype "bidirectional"))
    )
    (net (code "48") (name "ST-IO") (class "Default")
      (node (ref "IC2") (pin "34") (pinfunction "PA13_34") (pintype "bidirectional"))
    )
    (net (code "49") (name "TX-MIDI") (class "Default")
      (node (ref "IC2") (pin "12") (pinfunction "PA2_12") (pintype "bidirectional"))
    )
    (net (code "50") (name "WR") (class "Default")
      (node (ref "IC1") (pin "/WR") (pinfunction "/WR_/WR") (pintype "passive"))
      (node (ref "IC11") (pin "/WR") (pinfunction "/WR_/WR") (pintype "passive"))
      (node (ref "IC14") (pin "/WR") (pinfunction "/WR_/WR") (pintype "passive"))
      (node (ref "IC17") (pin "/WR") (pinfunction "/WR_/WR") (pintype "passive"))
      (node (ref "IC2") (pin "20") (pinfunction "PB2_20") (pintype "bidirectional"))
    )
    (net (code "51") (name "YM-CLK") (class "Default")
      (node (ref "IC1") (pin "SY") (pinfunction "SY_SY") (pintype "passive"))
      (node (ref "IC11") (pin "SY") (pinfunction "SY_SY") (pintype "passive"))
      (node (ref "IC12") (pin "CLK") (pinfunction "CLK_CLK") (pintype "passive"))
      (node (ref "IC14") (pin "SY") (pinfunction "SY_SY") (pintype "passive"))
      (node (ref "IC15") (pin "CLK") (pinfunction "CLK_CLK") (pintype "passive"))
      (node (ref "IC17") (pin "SY") (pinfunction "SY_SY") (pintype "passive"))
      (node (ref "IC18") (pin "CLK") (pinfunction "CLK_CLK") (pintype "passive"))
      (node (ref "IC6") (pin "CLK") (pinfunction "CLK_CLK") (pintype "passive"))
    )
    (net (code "52") (name "YM-RST") (class "Default")
      (node (ref "IC1") (pin "/IC") (pinfunction "/IC_/IC") (pintype "passive"))
      (node (ref "IC11") (pin "/IC") (pinfunction "/IC_/IC") (pintype "passive"))
      (node (ref "IC14") (pin "/IC") (pinfunction "/IC_/IC") (pintype "passive"))
      (node (ref "IC17") (pin "/IC") (pinfunction "/IC_/IC") (pintype "passive"))
      (node (ref "IC2") (pin "45") (pinfunction "PB8_45") (pintype "bidirectional"))
    )
    (net (code "53") (name "YM0-OUTPUT") (class "Default")
      (node (ref "IC1") (pin "MO") (pinfunction "MO_MO") (pintype "passive"))
      (node (ref "IC6") (pin "SD") (pinfunction "SD_SD") (pintype "passive"))
    )
    (net (code "54") (name "YM0-SYNC") (class "Default")
      (node (ref "IC1") (pin "SH") (pinfunction "SH_SH") (pintype "passive"))
      (node (ref "IC6") (pin "LOAD") (pinfunction "LOAD_LOAD") (pintype "passive"))
    )
    (net (code "55") (name "YM1-OUTPUT") (class "Default")
      (node (ref "IC11") (pin "MO") (pinfunction "MO_MO") (pintype "passive"))
      (node (ref "IC12") (pin "SD") (pinfunction "SD_SD") (pintype "passive"))
    )
    (net (code "56") (name "YM1-SYNC") (class "Default")
      (node (ref "IC11") (pin "SH") (pinfunction "SH_SH") (pintype "passive"))
      (node (ref "IC12") (pin "LOAD") (pinfunction "LOAD_LOAD") (pintype "passive"))
    )
    (net (code "57") (name "YM2-OUTPUT") (class "Default")
      (node (ref "IC14") (pin "MO") (pinfunction "MO_MO") (pintype "passive"))
      (node (ref "IC15") (pin "SD") (pinfunction "SD_SD") (pintype "passive"))
    )
    (net (code "58") (name "YM2-SYNC") (class "Default")
      (node (ref "IC14") (pin "SH") (pinfunction "SH_SH") (pintype "passive"))
      (node (ref "IC15") (pin "LOAD") (pinfunction "LOAD_LOAD") (pintype "passive"))
    )
    (net (code "59") (name "YM3-OUTPUT") (class "Default")
      (node (ref "IC17") (pin "MO") (pinfunction "MO_MO") (pintype "passive"))
      (node (ref "IC18") (pin "SD") (pinfunction "SD_SD") (pintype "passive"))
    )
    (net (code "60") (name "YM3-SYNC") (class "Default")
      (node (ref "IC17") (pin "SH") (pinfunction "SH_SH") (pintype "passive"))
      (node (ref "IC18") (pin "LOAD") (pinfunction "LOAD_LOAD") (pintype "passive"))
    )
    (net (code "61") (name "unconnected-(C28-Pad2)") (class "Default")
      (node (ref "C28") (pin "2") (pinfunction "2_2") (pintype "passive"))
    )
    (net (code "62") (name "unconnected-(C29-Pad2)") (class "Default")
      (node (ref "C29") (pin "2") (pinfunction "2_2") (pintype "passive"))
    )
    (net (code "63") (name "unconnected-(C30-Pad2)") (class "Default")
      (node (ref "C30") (pin "2") (pinfunction "2_2") (pintype "passive"))
    )
    (net (code "64") (name "unconnected-(IC1-NC-PadNC@1)") (class "Default")
      (node (ref "IC1") (pin "NC@1") (pinfunction "NC_NC@1") (pintype "passive"))
    )
    (net (code "65") (name "unconnected-(IC1-NC-PadNC@2)") (class "Default")
      (node (ref "IC1") (pin "NC@2") (pinfunction "NC_NC@2") (pintype "passive"))
    )
    (net (code "66") (name "unconnected-(IC1-NC-PadNC@3)") (class "Default")
      (node (ref "IC1") (pin "NC@3") (pinfunction "NC_NC@3") (pintype "passive"))
    )
    (net (code "67") (name "unconnected-(IC1-NC-PadNC@4)") (class "Default")
      (node (ref "IC1") (pin "NC@4") (pinfunction "NC_NC@4") (pintype "passive"))
    )
    (net (code "68") (name "unconnected-(IC1-PadM)") (class "Default")
      (node (ref "IC1") (pin "M") (pinfunction "M_M") (pintype "passive"))
    )
    (net (code "69") (name "unconnected-(IC1-Pad{slash}IRQ)") (class "Default")
      (node (ref "IC1") (pin "/IRQ") (pinfunction "/IRQ_/IRQ") (pintype "passive"))
    )
    (net (code "70") (name "unconnected-(IC2B-PA8-Pad29)") (class "Default")
      (node (ref "IC2") (pin "29") (pinfunction "PA8_29") (pintype "bidirectional"))
    )
    (net (code "71") (name "unconnected-(IC2B-PA9-Pad30)") (class "Default")
      (node (ref "IC2") (pin "30") (pinfunction "PA9_30") (pintype "bidirectional"))
    )
    (net (code "72") (name "unconnected-(IC2B-PA10-Pad31)") (class "Default")
      (node (ref "IC2") (pin "31") (pinfunction "PA10_31") (pintype "bidirectional"))
    )
    (net (code "73") (name "unconnected-(IC2B-PA11-Pad32)") (class "Default")
      (node (ref "IC2") (pin "32") (pinfunction "PA11_32") (pintype "bidirectional"))
    )
    (net (code "74") (name "unconnected-(IC2B-PA12-Pad33)") (class "Default")
      (node (ref "IC2") (pin "33") (pinfunction "PA12_33") (pintype "bidirectional"))
    )
    (net (code "75") (name "unconnected-(IC2B-PA15-Pad38)") (class "Default")
      (node (ref "IC2") (pin "38") (pinfunction "PA15_38") (pintype "bidirectional"))
    )
    (net (code "76") (name "unconnected-(IC2C-PA0-Pad10)") (class "Default")
      (node (ref "IC2") (pin "10") (pinfunction "PA0_10") (pintype "bidirectional"))
    )
    (net (code "77") (name "unconnected-(IC2C-PA1-Pad11)") (class "Default")
      (node (ref "IC2") (pin "11") (pinfunction "PA1_11") (pintype "bidirectional"))
    )
    (net (code "78") (name "unconnected-(IC2C-PA4-Pad14)") (class "Default")
      (node (ref "IC2") (pin "14") (pinfunction "PA4_14") (pintype "bidirectional"))
    )
    (net (code "79") (name "unconnected-(IC2C-PA5-Pad15)") (class "Default")
      (node (ref "IC2") (pin "15") (pinfunction "PA5_15") (pintype "bidirectional"))
    )
    (net (code "80") (name "unconnected-(IC2C-PA6-Pad16)") (class "Default")
      (node (ref "IC2") (pin "16") (pinfunction "PA6_16") (pintype "bidirectional"))
    )
    (net (code "81") (name "unconnected-(IC2C-PA7-Pad17)") (class "Default")
      (node (ref "IC2") (pin "17") (pinfunction "PA7_17") (pintype "bidirectional"))
    )
    (net (code "82") (name "unconnected-(IC2D-PB15-Pad28)") (class "Default")
      (node (ref "IC2") (pin "28") (pinfunction "PB15_28") (pintype "bidirectional"))
    )
    (net (code "83") (name "unconnected-(IC11-NC-PadNC@1)") (class "Default")
      (node (ref "IC11") (pin "NC@1") (pinfunction "NC_NC@1") (pintype "passive"))
    )
    (net (code "84") (name "unconnected-(IC11-NC-PadNC@2)") (class "Default")
      (node (ref "IC11") (pin "NC@2") (pinfunction "NC_NC@2") (pintype "passive"))
    )
    (net (code "85") (name "unconnected-(IC11-NC-PadNC@3)") (class "Default")
      (node (ref "IC11") (pin "NC@3") (pinfunction "NC_NC@3") (pintype "passive"))
    )
    (net (code "86") (name "unconnected-(IC11-NC-PadNC@4)") (class "Default")
      (node (ref "IC11") (pin "NC@4") (pinfunction "NC_NC@4") (pintype "passive"))
    )
    (net (code "87") (name "unconnected-(IC11-PadM)") (class "Default")
      (node (ref "IC11") (pin "M") (pinfunction "M_M") (pintype "passive"))
    )
    (net (code "88") (name "unconnected-(IC11-Pad{slash}IRQ)") (class "Default")
      (node (ref "IC11") (pin "/IRQ") (pinfunction "/IRQ_/IRQ") (pintype "passive"))
    )
    (net (code "89") (name "unconnected-(IC14-NC-PadNC@1)") (class "Default")
      (node (ref "IC14") (pin "NC@1") (pinfunction "NC_NC@1") (pintype "passive"))
    )
    (net (code "90") (name "unconnected-(IC14-NC-PadNC@2)") (class "Default")
      (node (ref "IC14") (pin "NC@2") (pinfunction "NC_NC@2") (pintype "passive"))
    )
    (net (code "91") (name "unconnected-(IC14-NC-PadNC@3)") (class "Default")
      (node (ref "IC14") (pin "NC@3") (pinfunction "NC_NC@3") (pintype "passive"))
    )
    (net (code "92") (name "unconnected-(IC14-NC-PadNC@4)") (class "Default")
      (node (ref "IC14") (pin "NC@4") (pinfunction "NC_NC@4") (pintype "passive"))
    )
    (net (code "93") (name "unconnected-(IC14-PadM)") (class "Default")
      (node (ref "IC14") (pin "M") (pinfunction "M_M") (pintype "passive"))
    )
    (net (code "94") (name "unconnected-(IC14-Pad{slash}IRQ)") (class "Default")
      (node (ref "IC14") (pin "/IRQ") (pinfunction "/IRQ_/IRQ") (pintype "passive"))
    )
    (net (code "95") (name "unconnected-(IC17-NC-PadNC@1)") (class "Default")
      (node (ref "IC17") (pin "NC@1") (pinfunction "NC_NC@1") (pintype "passive"))
    )
    (net (code "96") (name "unconnected-(IC17-NC-PadNC@2)") (class "Default")
      (node (ref "IC17") (pin "NC@2") (pinfunction "NC_NC@2") (pintype "passive"))
    )
    (net (code "97") (name "unconnected-(IC17-NC-PadNC@3)") (class "Default")
      (node (ref "IC17") (pin "NC@3") (pinfunction "NC_NC@3") (pintype "passive"))
    )
    (net (code "98") (name "unconnected-(IC17-NC-PadNC@4)") (class "Default")
      (node (ref "IC17") (pin "NC@4") (pinfunction "NC_NC@4") (pintype "passive"))
    )
    (net (code "99") (name "unconnected-(IC17-PadM)") (class "Default")
      (node (ref "IC17") (pin "M") (pinfunction "M_M") (pintype "passive"))
    )
    (net (code "100") (name "unconnected-(IC17-Pad{slash}IRQ)") (class "Default")
      (node (ref "IC17") (pin "/IRQ") (pinfunction "/IRQ_/IRQ") (pintype "passive"))
    )
    (net (code "101") (name "unconnected-(JP2-Pad6)") (class "Default")
      (node (ref "JP2") (pin "6") (pinfunction "6_6") (pintype "passive"))
    )
  )
)
